# Fonte.net
KiCad netlist of a schematic drawn in Altium Designer
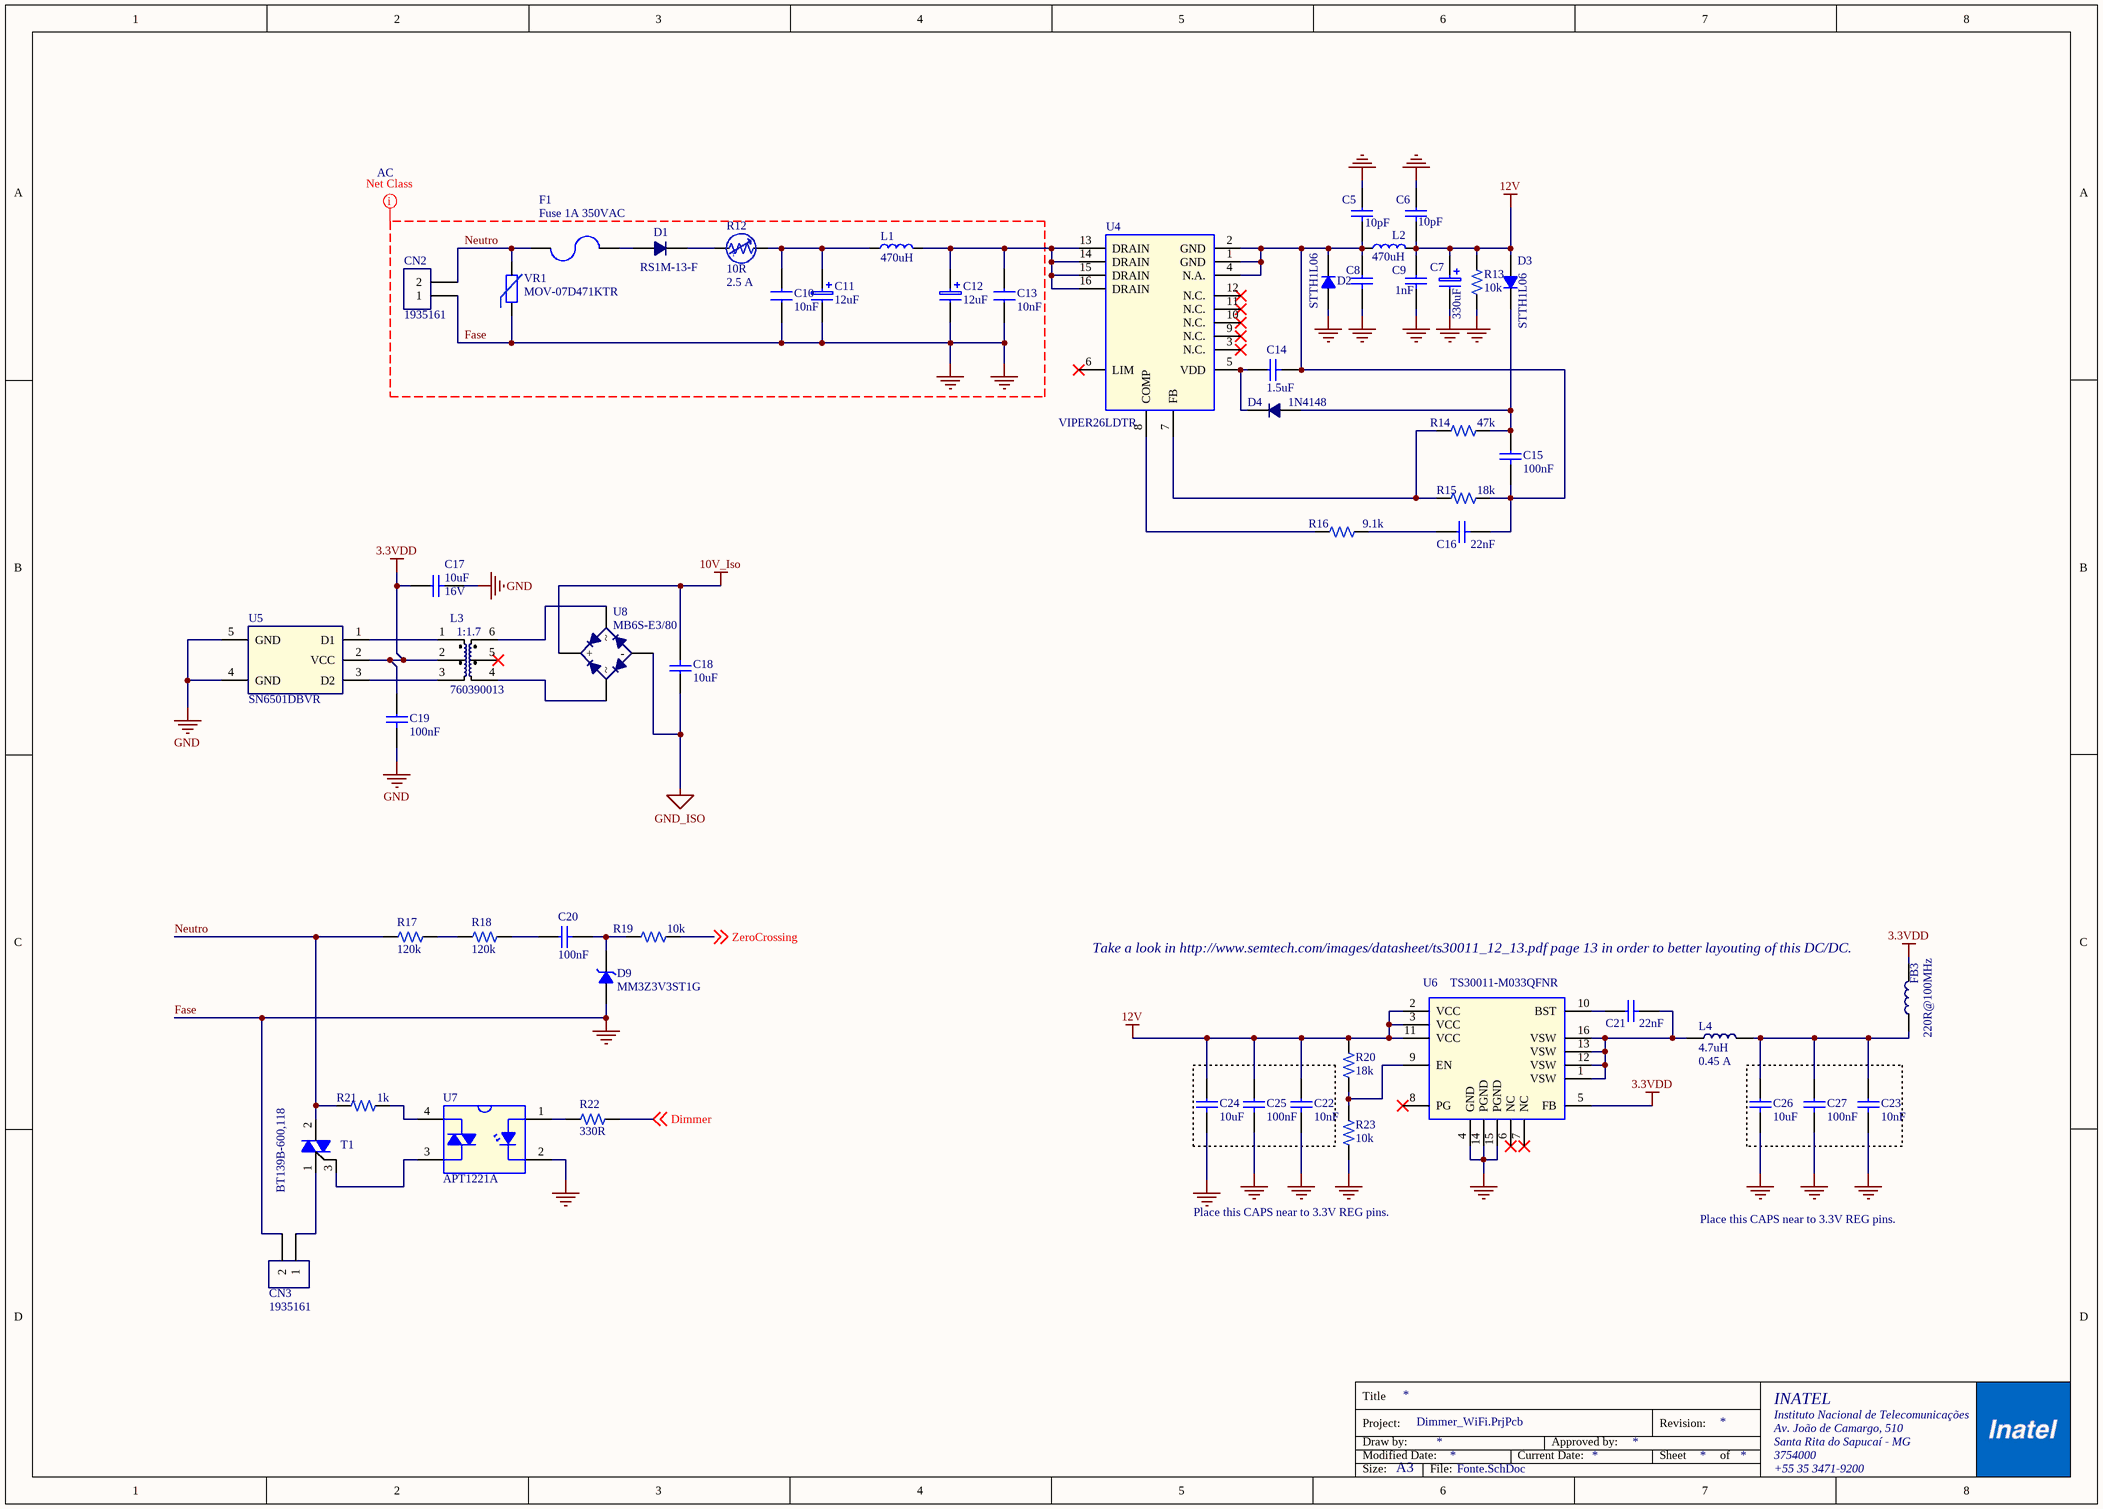
[diagram p0: Fonte.SchDoc]

(export (version "E")
  (design (tool "Eeschema 10.0.6"))
  (components
    (comp (ref "C5")
      (value "10pF")
      (footprint "0603-3D")
      (description "CAP CER 10PF 50V NP0 0603")
      (fields (field (name "VOLTAGE") "50V") (field (name "USER") "Rodrigo Villela"))
      (libsource (lib "CapacitoresPrjLib") (part "10pF 1% 0603 MLCC NPO 50V"))
    )
    (comp (ref "C6")
      (value "10pF")
      (footprint "0603-3D")
      (description "CAP CER 10PF 50V NP0 0603")
      (fields (field (name "VOLTAGE") "50V") (field (name "USER") "Rodrigo Villela"))
      (libsource (lib "CapacitoresPrjLib") (part "10pF 1% 0603 MLCC NPO 50V"))
    )
    (comp (ref "C7")
      (value "330uF")
      (footprint "CAP-RADIAL-630Dx1500Hx250P-3D")
      (description "CAP 330 UF 20% 16 V")
      (fields (field (name "VOLTAGE") "16V") (field (name "USER") "Jean Pierre"))
      (libsource (lib "LES") (part "330uF 20% RADIAL PTH 16V"))
    )
    (comp (ref "C8")
      (value "1nF")
      (footprint "0603-3D")
      (description "CAP CER 1000PF 50V 5% NP0 0603")
      (fields (field (name "VOLTAGE") "50V") (field (name "USER") "Anderson Daniel Soares"))
      (libsource (lib "CapacitoresPrjLib") (part "1000pF 5% 0603 MLCC NP0 50V"))
    )
    (comp (ref "C9")
      (value "1nF")
      (footprint "0603-3D")
      (description "CAP CER 1000PF 50V 5% NP0 0603")
      (fields (field (name "VOLTAGE") "50V") (field (name "USER") "Anderson Daniel Soares"))
      (libsource (lib "CapacitoresPrjLib") (part "1000pF 5% 0603 MLCC NP0 50V"))
    )
    (comp (ref "C10")
      (value "10nF")
      (footprint "CAP-RADIAL-5mm")
      (description "CAP FILM 10000PF 5% 630VDC RAD")
      (fields (field (name "VOLTAGE") "400VAC") (field (name "USER") "Ricardo Dias"))
      (libsource (lib "CapacitoresPrjLib") (part "10nF 5% RADIAL FILM 400VAC"))
    )
    (comp (ref "C11")
      (value "12uF")
      (footprint "CAP-RADIAL-1000Dx1750Hx500P-3D")
      (description "CAP ALUM 12UF 20% 350V RADIAL")
      (fields (field (name "VOLTAGE") "350V") (field (name "USER") "Ricardo Dias"))
      (libsource (lib "LES") (part "12uF 20% RADIAL PTH 350V"))
    )
    (comp (ref "C12")
      (value "12uF")
      (footprint "CAP-RADIAL-1000Dx1750Hx500P-3D")
      (description "CAP ALUM 12UF 20% 350V RADIAL")
      (fields (field (name "VOLTAGE") "350V") (field (name "USER") "Ricardo Dias"))
      (libsource (lib "LES") (part "12uF 20% RADIAL PTH 350V"))
    )
    (comp (ref "C13")
      (value "10nF")
      (footprint "CAP-RADIAL-5mm")
      (description "CAP FILM 10000PF 5% 630VDC RAD")
      (fields (field (name "VOLTAGE") "400VAC") (field (name "USER") "Ricardo Dias"))
      (libsource (lib "CapacitoresPrjLib") (part "10nF 5% RADIAL FILM 400VAC"))
    )
    (comp (ref "C14")
      (value "1.5uF")
      (footprint "1206-Ceramic-3D")
      (description "CAP CER 1.5UF 50V X7R 1206")
      (fields (field (name "VOLTAGE") "50V") (field (name "USER") "Ricardo Dias"))
      (libsource (lib "LES") (part "1.5uF 10% 1206 MLCC X7R 50V"))
    )
    (comp (ref "C15")
      (value "100nF")
      (footprint "0603-3D")
      (description "0.1µF ±10% 50V Ceramic Capacitor X7R 0603 (1608 Metric)")
      (fields (field (name "VOLTAGE") "50V") (field (name "USER") "Ricardo Dias"))
      (libsource (lib "CapacitoresPrjLib") (part "0.1uF 10% 0603 MLCC X7R 50V KEMET"))
    )
    (comp (ref "C16")
      (value "22nF")
      (footprint "0603-3D")
      (description "0.022µF 16V Ceramic Capacitor X7R 0603")
      (fields (field (name "VOLTAGE") "16V") (field (name "USER") "Jean Pierre"))
      (libsource (lib "CapacitoresPrjLib") (part "0.022uF 20% 0603 MLCC X7R 16V"))
    )
    (comp (ref "C17")
      (value "10uF")
      (footprint "CAP-0603-3D")
      (description "CAP CER 10UF 16V 20% X5R 0603")
      (fields (field (name "VOLTAGE") "16V") (field (name "USER") "Mateus Elias"))
      (libsource (lib "CapacitoresPrjLib") (part "10uF 20% 0603 MLCC X5R 16V"))
    )
    (comp (ref "C18")
      (value "10uF")
      (footprint "CAP-0603-3D")
      (description "CAP CER 10UF 16V 20% X5R 0603")
      (fields (field (name "VOLTAGE") "16V") (field (name "USER") "Mateus Elias"))
      (libsource (lib "CapacitoresPrjLib") (part "10uF 20% 0603 MLCC X5R 16V"))
    )
    (comp (ref "C19")
      (value "100nF")
      (footprint "0603-3D")
      (description "CAP CER 0.1UF 50V 10% X7R 0603")
      (fields (field (name "VOLTAGE") "50V") (field (name "USER") "Anderson Daniel Soares"))
      (libsource (lib "CapacitoresPrjLib") (part "0.1uF 10% 0603 MLCC X7R 50V"))
    )
    (comp (ref "C20")
      (value "100nF")
      (footprint "0603-3D")
      (description "CAP CER 0.1UF 50V 10% X7R 0603")
      (fields (field (name "VOLTAGE") "50V") (field (name "USER") "Anderson Daniel Soares"))
      (libsource (lib "CapacitoresPrjLib") (part "0.1uF 10% 0603 MLCC X7R 50V"))
    )
    (comp (ref "C21")
      (value "22nF")
      (footprint "0603-3D")
      (description "0.022µF 16V Ceramic Capacitor X7R 0603")
      (fields (field (name "VOLTAGE") "16V") (field (name "USER") "Jean Pierre"))
      (libsource (lib "CapacitoresPrjLib") (part "0.022uF 20% 0603 MLCC X7R 16V"))
    )
    (comp (ref "C22")
      (value "10nF")
      (footprint "0603-3D")
      (description "10000pF ±10% 16V Ceramic Capacitor X7R 0603 (1608 Metric)")
      (fields (field (name "VOLTAGE") "50V") (field (name "USER") "Ricardo Dias"))
      (libsource (lib "CapacitoresPrjLib") (part "10000pF 10% 0603 MLCC X7R 50V KEMET"))
    )
    (comp (ref "C23")
      (value "10nF")
      (footprint "0603-3D")
      (description "10000pF ±10% 16V Ceramic Capacitor X7R 0603 (1608 Metric)")
      (fields (field (name "VOLTAGE") "50V") (field (name "USER") "Ricardo Dias"))
      (libsource (lib "CapacitoresPrjLib") (part "10000pF 10% 0603 MLCC X7R 50V KEMET"))
    )
    (comp (ref "C24")
      (value "10uF")
      (footprint "CAP-0603-3D")
      (description "CAP CER 10UF 16V 20% X5R 0603")
      (fields (field (name "VOLTAGE") "16V") (field (name "USER") "Mateus Elias"))
      (libsource (lib "CapacitoresPrjLib") (part "10uF 20% 0603 MLCC X5R 16V"))
    )
    (comp (ref "C25")
      (value "100nF")
      (footprint "0603-3D")
      (description "CAP CER 0.1UF 50V 10% X7R 0603")
      (fields (field (name "VOLTAGE") "50V") (field (name "USER") "Anderson Daniel Soares"))
      (libsource (lib "CapacitoresPrjLib") (part "0.1uF 10% 0603 MLCC X7R 50V"))
    )
    (comp (ref "C26")
      (value "10uF")
      (footprint "CAP-0603-3D")
      (description "CAP CER 10UF 16V 20% X5R 0603")
      (fields (field (name "VOLTAGE") "16V") (field (name "USER") "Mateus Elias"))
      (libsource (lib "CapacitoresPrjLib") (part "10uF 20% 0603 MLCC X5R 16V"))
    )
    (comp (ref "C27")
      (value "100nF")
      (footprint "0603-3D")
      (description "CAP CER 0.1UF 50V 10% X7R 0603")
      (fields (field (name "VOLTAGE") "50V") (field (name "USER") "Anderson Daniel Soares"))
      (libsource (lib "CapacitoresPrjLib") (part "0.1uF 10% 0603 MLCC X7R 50V"))
    )
    (comp (ref "CN2")
      (value "1935161")
      (footprint "TERM BLOCK PCB 2POS 5.0MM")
      (description "TERM BLOCK PCB 2POS 5.0MM")
      (fields (field (name "USER") "Rodrigo Balbi"))
      (libsource (lib "") (part "1935161  TERM BLOCK PCB 2X1_1"))
    )
    (comp (ref "CN3")
      (value "1935161")
      (footprint "TERM BLOCK PCB 2POS 5.0MM")
      (description "TERM BLOCK PCB 2POS 5.0MM")
      (fields (field (name "USER") "Rodrigo Balbi"))
      (libsource (lib "Conectores") (part "1935161  TERM BLOCK PCB 2X1"))
    )
    (comp (ref "D1")
      (value "RS1M-13-F")
      (footprint "DO-214AC_SMA-3D")
      (description "DIODE GEN PURP 1KV 1A SMA")
      (fields (field (name "MANUFACTURER") "Diodes Incorporated") (field (name "USER") "Pedro Vilela"))
      (libsource (lib "Diodos") (part "RS1M-13-F DIODE GEN PURP 1KV 1A SMA"))
    )
    (comp (ref "D2")
      (value "STTH1L06")
      (footprint "DO-214AC_SMA-3D")
      (description "DIODE GEN PURP 600V 1A SMA")
      (fields (field (name "USER") "Rafael Magalhães de Barros"))
      (libsource (lib "Diodos") (part "STTH1L06 TURBO 2 ULTRAFAST HIGH VOLTAGE RECTIFIER"))
    )
    (comp (ref "D3")
      (value "STTH1L06")
      (footprint "DO-214AC_SMA-3D")
      (description "DIODE GEN PURP 600V 1A SMA")
      (fields (field (name "USER") "Rafael Magalhães de Barros"))
      (libsource (lib "Diodos") (part "STTH1L06 TURBO 2 ULTRAFAST HIGH VOLTAGE RECTIFIER"))
    )
    (comp (ref "D4")
      (value "1N4148")
      (footprint "SOD323-3D")
      (description "DIODE SWITCHING 75V 0.15A SOD323")
      (fields (field (name "USER") "Mateus Elias"))
      (libsource (lib "Diodos") (part "1N4148 FAST SWITCHING DIODE"))
    )
    (comp (ref "D9")
      (value "MM3Z3V3ST1G")
      (footprint "SOD323-3D")
      (description "DIODE ZENER 3.3V 200MW SOD323")
      (fields (field (name "USER") "Ricardo Dias"))
      (libsource (lib "LES") (part "MM3Z3V3ST1G 3.3V DIODE ZENER"))
    )
    (comp (ref "F1")
      (value "Fuse 1A 350VAC")
      (footprint "Fuse-SMD-610L254W279H-3D")
      (description "FUSE BOARD MNT 1A 350VAC 72VDC")
      (fields (field (name "USER") "Mateus Elias"))
      (libsource (lib "DiversosPrjLib") (part "Fuse Board SMD2410 350VAC 72VDC"))
    )
    (comp (ref "FB3")
      (value "220R@100MHz")
      (footprint "IND-0603-3D")
      (description "FERRITE CHIP 0603 220 OHM")
      (fields (field (name "USER") "Jean Pierre"))
      (libsource (lib "IndutoresPrjLib") (part "220R@100MHz 0603 FB 0.05R 2A"))
    )
    (comp (ref "L1")
      (value "470uH")
      (footprint "IND_620W590L450H_CLF6045")
      (description "FIXED IND 470UH 370MA 1.42 OHM")
      (fields (field (name "USER") "Jean Pierre"))
      (libsource (lib "LES") (part "470uH 20% SMDPWR WW 0.37A"))
    )
    (comp (ref "L2")
      (value "470uH")
      (footprint "IND_620W590L450H_CLF6045")
      (description "FIXED IND 470UH 370MA 1.42 OHM")
      (fields (field (name "USER") "Jean Pierre"))
      (libsource (lib "LES") (part "470uH 20% SMDPWR WW 0.37A"))
    )
    (comp (ref "L3")
      (value "760390013")
      (footprint "TRAFO-DC/DC-CONVERTERS-3D")
      (description "TRANSFORMER 475UH SMD")
      (fields (field (name "USER") "Ricardo Dias"))
      (libsource (lib "IndutoresPrjLib") (part "760390013 TRANSFORMER 475UH SMD"))
    )
    (comp (ref "L4")
      (value "4.7uH")
      (footprint "IND-1210-PWR-3D")
      (description "FIXED IND 4.7UH 450MA 200 MOHM")
      (fields (field (name "CURRENT RATING") "0.45 A") (field (name "USER") "Jean Pierre"))
      (libsource (lib "IndutoresPrjLib") (part "4.7uH SMD WW 0.2R 0.45A"))
    )
    (comp (ref "R12")
      (value "10R")
      (footprint "NTC-800D500W-500P-3D")
      (description "ICL 10 OHM 20% 2.5A 8MM")
      (fields
        (field (name "TOLERANCE") "20%")
        (field (name "CURRENT") "2.5 A")
        (field (name "USER") "Jean Pierre")
      )
      (libsource (lib "DiversosPrjLib") (part "SL08 10002 NTC 10R 20% 2.5A 8MM"))
    )
    (comp (ref "R13")
      (value "10k")
      (footprint "0603-3D")
      (description "RES SMD 10K OHM 1% 1/10W 0603")
      (fields
        (field (name "MANUFACTURER") "Yageo")
        (field (name "MANUFACTURER PART NUMBER") "RC0603FR-0710KL")
        (field (name "USER") "Pedro Vilela")
      )
      (libsource (lib "ResitoresPrjLib") (part "10k 1% 0603 TNF 1/10W"))
    )
    (comp (ref "R14")
      (value "47k")
      (footprint "0603-3D")
      (description "RES SMD 47K OHM 1% 1/10W 0603")
      (fields (field (name "USER") "Anderson Daniel Soares"))
      (libsource (lib "ResitoresPrjLib") (part "47k 1% 0603 TKF 1/16W"))
    )
    (comp (ref "R15")
      (value "18k")
      (footprint "0603-3D")
      (description "RES SMD 18K OHM 1% 1/10W 0603")
      (fields (field (name "TOLERANCE") "1%") (field (name "USER") "Ricardo Dias"))
      (libsource (lib "ResitoresPrjLib") (part "18k 1% 0603 TKF 1/10W"))
    )
    (comp (ref "R16")
      (value "9.1k")
      (footprint "0603-3D")
      (description "RES SMD 9.1K OHM 1% 1/10W 0603")
      (fields (field (name "USER") "Ricardo Dias"))
      (libsource (lib "ResitoresPrjLib") (part "9.1k 1% 0603 TKF 1/10W"))
    )
    (comp (ref "R17")
      (value "120k")
      (footprint "RES-1206-3D")
      (description "RES SMD 120K OHM 5% 1/4W 1206")
      (fields (field (name "TOLERANCE") "5%") (field (name "USER") "Rodrigo Villela"))
      (libsource (lib "ResitoresPrjLib") (part "120k 5% 1206 TKF 1/4W"))
    )
    (comp (ref "R18")
      (value "120k")
      (footprint "RES-1206-3D")
      (description "RES SMD 120K OHM 5% 1/4W 1206")
      (fields (field (name "TOLERANCE") "5%") (field (name "USER") "Rodrigo Villela"))
      (libsource (lib "ResitoresPrjLib") (part "120k 5% 1206 TKF 1/4W"))
    )
    (comp (ref "R19")
      (value "10k")
      (footprint "0603-3D")
      (description "RES SMD 10K OHM 1% 1/10W 0603")
      (fields
        (field (name "MANUFACTURER") "Yageo")
        (field (name "MANUFACTURER PART NUMBER") "RC0603FR-0710KL")
        (field (name "USER") "Pedro Vilela")
      )
      (libsource (lib "ResitoresPrjLib") (part "10k 1% 0603 TNF 1/10W"))
    )
    (comp (ref "R20")
      (value "18k")
      (footprint "0603-3D")
      (description "RES SMD 18K OHM 1% 1/10W 0603")
      (fields (field (name "TOLERANCE") "1%") (field (name "USER") "Ricardo Dias"))
      (libsource (lib "ResitoresPrjLib") (part "18k 1% 0603 TKF 1/10W"))
    )
    (comp (ref "R21")
      (value "1k")
      (footprint "0805-3D")
      (description "RES SMD 1K OHM 1% 1/8W 0805")
      (fields (field (name "USER") "Mateus Elias"))
      (libsource (lib "ResitoresPrjLib") (part "1k 1% 0805 TKF 1/8W"))
    )
    (comp (ref "R22")
      (value "330R")
      (footprint "0603-3D")
      (description "RES SMD 330 OHM 5% 1/10W 0603")
      (fields (field (name "TOLERANCE") "5%") (field (name "USER") "Luiz F Siecola"))
      (libsource (lib "ResitoresPrjLib") (part "330R 5% 0603 TKF 1/10W"))
    )
    (comp (ref "R23")
      (value "10k")
      (footprint "0603-3D")
      (description "RES SMD 10K OHM 1% 1/10W 0603")
      (fields
        (field (name "MANUFACTURER") "Yageo")
        (field (name "MANUFACTURER PART NUMBER") "RC0603FR-0710KL")
        (field (name "USER") "Pedro Vilela")
      )
      (libsource (lib "ResitoresPrjLib") (part "10k 1% 0603 TNF 1/10W"))
    )
    (comp (ref "T1")
      (value "BT139B-600,118")
      (footprint "D2PAC-3D")
      (description "TRIAC 600V 16A D2PAK")
      (fields (field (name "USER") "Jean Pierre"))
      (libsource (lib "Transistores") (part "BT139B-600,118 TRIAC GEN PURPOSE"))
    )
    (comp (ref "U4")
      (value "VIPER26LDTR")
      (footprint "SO16N-3D")
      (description "IC OFFLINE CONV PWM 800V 16-SOIC")
      (fields (field (name "USER") "Ricardo Dias"))
      (libsource (lib "LES") (part "VIPER26LDTR CONVERTER CA/CC FIXED FREQ"))
    )
    (comp (ref "U5")
      (value "SN6501DBVR")
      (footprint "SOT23-5")
      (description "IC REG CONV PWR SUPPLIES SOT23-5")
      (fields (field (name "USER") "Ricardo Dias"))
      (libsource (lib "Circuito Integrado") (part "SN6501DBVR REG CONV ISO PWR SUPPLIES SOT23-5"))
    )
    (comp (ref "U6")
      (value "TS30011-M033QFNR")
      (footprint "16VQFN-3D")
      (description "IC REG BUCK 3.3V 1A SYNC 16-VQFN")
      (fields (field (name "USER") "Ricardo Dias"))
      (libsource (lib "LES") (part "TS30011-M033QFNR DC/DC 3.3V FIX 1A 1.5MHz"))
    )
    (comp (ref "U7")
      (value "APT1221A")
      (footprint "DIP4-SMD")
      (description "Optoisolator Triac Output 5000Vrms 1 Channel 4-SMD")
      (fields (field (name "USER") "Luiz Fernando"))
      (libsource (lib "Circuito Integrado") (part "APT1221A"))
    )
    (comp (ref "U8")
      (value "MB6S-E3/80")
      (footprint "TO-269AA-3D")
      (description "Bridge Rectifier Single Phase 600V 500mA Surface Mount TO-269AA (MBS)")
      (fields (field (name "USER") "Reis"))
      (libsource (lib "Diodos") (part "MB6S-E3/80 BRIDGE RECTIFIER SINGLE"))
    )
    (comp (ref "VR1")
      (value "MOV-07D471KTR")
      (footprint "VAR-05D-SERIES-PTH-3D")
      (description "MOV-07D471KTR - VARISTOR 470V 1.2KA DISC 7MM")
      (fields (field (name "USER") "Luiz F Siecola"))
      (libsource (lib "DiversosPrjLib") (part "MOV-07D471KTR VAR 470V 1.2KA DISC 7MM"))
    )
  )
  (nets
    (net (code "1") (name "/Neutro") (class "Default")
      (node (ref "CN2") (pin "2") (pinfunction "2_2") (pintype "passive"))
      (node (ref "F1") (pin "2") (pinfunction "2_2") (pintype "passive"))
      (node (ref "R17") (pin "1") (pinfunction "1_1") (pintype "passive"))
      (node (ref "R21") (pin "2") (pinfunction "2_2") (pintype "passive"))
      (node (ref "T1") (pin "2") (pinfunction "T2_2") (pintype "passive"))
      (node (ref "VR1") (pin "2") (pinfunction "2_2") (pintype "passive"))
    )
    (net (code "2") (name "3.3VDD") (class "Default")
      (node (ref "C17") (pin "1") (pinfunction "1_1") (pintype "passive"))
      (node (ref "C19") (pin "1") (pinfunction "1_1") (pintype "passive"))
      (node (ref "FB3") (pin "2") (pinfunction "2_2") (pintype "passive"))
      (node (ref "L3") (pin "2") (pinfunction "2_2") (pintype "passive"))
      (node (ref "U5") (pin "2") (pinfunction "VCC_2") (pintype "passive"))
      (node (ref "U6") (pin "5") (pinfunction "FB_5") (pintype "passive"))
    )
    (net (code "3") (name "10V_Iso") (class "Default")
      (node (ref "C18") (pin "2") (pinfunction "2_2") (pintype "passive"))
      (node (ref "U8") (pin "3") (pinfunction "+_3") (pintype "passive"))
    )
    (net (code "4") (name "12V") (class "Default")
      (node (ref "C22") (pin "1") (pinfunction "1_1") (pintype "passive"))
      (node (ref "C24") (pin "1") (pinfunction "1_1") (pintype "passive"))
      (node (ref "C25") (pin "1") (pinfunction "1_1") (pintype "passive"))
      (node (ref "C6") (pin "2") (pinfunction "2_2") (pintype "passive"))
      (node (ref "C7") (pin "1") (pinfunction "1_1") (pintype "passive"))
      (node (ref "C9") (pin "1") (pinfunction "1_1") (pintype "passive"))
      (node (ref "D3") (pin "1") (pinfunction "1_1") (pintype "passive"))
      (node (ref "L2") (pin "2") (pinfunction "2_2") (pintype "passive"))
      (node (ref "R13") (pin "2") (pinfunction "2_2") (pintype "passive"))
      (node (ref "R20") (pin "2") (pinfunction "2_2") (pintype "passive"))
      (node (ref "U6") (pin "11") (pinfunction "VCC_11") (pintype "passive"))
      (node (ref "U6") (pin "2") (pinfunction "VCC_2") (pintype "passive"))
      (node (ref "U6") (pin "3") (pinfunction "VCC_3") (pintype "passive"))
    )
    (net (code "5") (name "Dimmer") (class "Default")
      (node (ref "R22") (pin "2") (pinfunction "2_2") (pintype "passive"))
    )
    (net (code "6") (name "GND") (class "Default")
      (node (ref "C10") (pin "2") (pinfunction "2_2") (pintype "passive"))
      (node (ref "C11") (pin "2") (pinfunction "2_2") (pintype "passive"))
      (node (ref "C12") (pin "2") (pinfunction "2_2") (pintype "passive"))
      (node (ref "C13") (pin "2") (pinfunction "2_2") (pintype "passive"))
      (node (ref "C17") (pin "2") (pinfunction "2_2") (pintype "passive"))
      (node (ref "C19") (pin "2") (pinfunction "2_2") (pintype "passive"))
      (node (ref "C22") (pin "2") (pinfunction "2_2") (pintype "passive"))
      (node (ref "C23") (pin "2") (pinfunction "2_2") (pintype "passive"))
      (node (ref "C24") (pin "2") (pinfunction "2_2") (pintype "passive"))
      (node (ref "C25") (pin "2") (pinfunction "2_2") (pintype "passive"))
      (node (ref "C26") (pin "2") (pinfunction "2_2") (pintype "passive"))
      (node (ref "C27") (pin "2") (pinfunction "2_2") (pintype "passive"))
      (node (ref "C5") (pin "1") (pinfunction "1_1") (pintype "passive"))
      (node (ref "C6") (pin "1") (pinfunction "1_1") (pintype "passive"))
      (node (ref "C7") (pin "2") (pinfunction "2_2") (pintype "passive"))
      (node (ref "C8") (pin "2") (pinfunction "2_2") (pintype "passive"))
      (node (ref "C9") (pin "2") (pinfunction "2_2") (pintype "passive"))
      (node (ref "CN2") (pin "1") (pinfunction "1_1") (pintype "passive"))
      (node (ref "CN3") (pin "2") (pinfunction "2_2") (pintype "passive"))
      (node (ref "D2") (pin "1") (pinfunction "1_1") (pintype "passive"))
      (node (ref "D9") (pin "1") (pinfunction "1_1") (pintype "passive"))
      (node (ref "R13") (pin "1") (pinfunction "1_1") (pintype "passive"))
      (node (ref "R23") (pin "1") (pinfunction "1_1") (pintype "passive"))
      (node (ref "U5") (pin "4") (pinfunction "GND_4") (pintype "passive"))
      (node (ref "U5") (pin "5") (pinfunction "GND_5") (pintype "passive"))
      (node (ref "U6") (pin "14") (pinfunction "PGND_14") (pintype "passive"))
      (node (ref "U6") (pin "15") (pinfunction "PGND_15") (pintype "passive"))
      (node (ref "U6") (pin "4") (pinfunction "GND_4") (pintype "passive"))
      (node (ref "U7") (pin "2") (pinfunction "K_2") (pintype "passive"))
      (node (ref "VR1") (pin "1") (pinfunction "1_1") (pintype "passive"))
    )
    (net (code "7") (name "GND_ISO") (class "Default")
      (node (ref "C18") (pin "1") (pinfunction "1_1") (pintype "passive"))
      (node (ref "U8") (pin "4") (pinfunction "-_4") (pintype "passive"))
    )
    (net (code "8") (name "Net-(C10-Pad1)") (class "Default")
      (node (ref "C10") (pin "1") (pinfunction "1_1") (pintype "passive"))
      (node (ref "C11") (pin "1") (pinfunction "1_1") (pintype "passive"))
      (node (ref "L1") (pin "1") (pinfunction "1_1") (pintype "passive"))
      (node (ref "R12") (pin "2") (pinfunction "2_2") (pintype "passive"))
    )
    (net (code "9") (name "Net-(C12-Pad1)") (class "Default")
      (node (ref "C12") (pin "1") (pinfunction "1_1") (pintype "passive"))
      (node (ref "C13") (pin "1") (pinfunction "1_1") (pintype "passive"))
      (node (ref "L1") (pin "2") (pinfunction "2_2") (pintype "passive"))
      (node (ref "U4") (pin "13") (pinfunction "DRAIN_13") (pintype "passive"))
      (node (ref "U4") (pin "14") (pinfunction "DRAIN_14") (pintype "passive"))
      (node (ref "U4") (pin "15") (pinfunction "DRAIN_15") (pintype "passive"))
      (node (ref "U4") (pin "16") (pinfunction "DRAIN_16") (pintype "passive"))
    )
    (net (code "10") (name "Net-(C15-Pad1)") (class "Default")
      (node (ref "C15") (pin "1") (pinfunction "1_1") (pintype "passive"))
      (node (ref "D3") (pin "2") (pinfunction "2_2") (pintype "passive"))
      (node (ref "D4") (pin "1") (pinfunction "1_1") (pintype "passive"))
      (node (ref "R14") (pin "2") (pinfunction "2_2") (pintype "passive"))
    )
    (net (code "11") (name "Net-(C16-Pad1)") (class "Default")
      (node (ref "C16") (pin "1") (pinfunction "1_1") (pintype "passive"))
      (node (ref "R16") (pin "2") (pinfunction "2_2") (pintype "passive"))
    )
    (net (code "12") (name "Net-(C20-Pad1)") (class "Default")
      (node (ref "C20") (pin "1") (pinfunction "1_1") (pintype "passive"))
      (node (ref "R18") (pin "2") (pinfunction "2_2") (pintype "passive"))
    )
    (net (code "13") (name "Net-(C20-Pad2)") (class "Default")
      (node (ref "C20") (pin "2") (pinfunction "2_2") (pintype "passive"))
      (node (ref "D9") (pin "2") (pinfunction "2_2") (pintype "passive"))
      (node (ref "R19") (pin "1") (pinfunction "1_1") (pintype "passive"))
    )
    (net (code "14") (name "Net-(C21-Pad2)") (class "Default")
      (node (ref "C21") (pin "2") (pinfunction "2_2") (pintype "passive"))
      (node (ref "L4") (pin "1") (pinfunction "1_1") (pintype "passive"))
      (node (ref "U6") (pin "1") (pinfunction "VSW_1") (pintype "passive"))
      (node (ref "U6") (pin "12") (pinfunction "VSW_12") (pintype "passive"))
      (node (ref "U6") (pin "13") (pinfunction "VSW_13") (pintype "passive"))
      (node (ref "U6") (pin "16") (pinfunction "VSW_16") (pintype "passive"))
    )
    (net (code "15") (name "Net-(C23-Pad1)") (class "Default")
      (node (ref "C23") (pin "1") (pinfunction "1_1") (pintype "passive"))
      (node (ref "C26") (pin "1") (pinfunction "1_1") (pintype "passive"))
      (node (ref "C27") (pin "1") (pinfunction "1_1") (pintype "passive"))
      (node (ref "FB3") (pin "1") (pinfunction "1_1") (pintype "passive"))
      (node (ref "L4") (pin "2") (pinfunction "2_2") (pintype "passive"))
    )
    (net (code "16") (name "Net-(D1-Pad1)") (class "Default")
      (node (ref "D1") (pin "1") (pinfunction "1_1") (pintype "passive"))
      (node (ref "F1") (pin "1") (pinfunction "1_1") (pintype "passive"))
    )
    (net (code "17") (name "Net-(D1-Pad2)") (class "Default")
      (node (ref "D1") (pin "2") (pinfunction "2_2") (pintype "passive"))
      (node (ref "R12") (pin "1") (pinfunction "1_1") (pintype "passive"))
    )
    (net (code "18") (name "Net-(L3-Pad4)") (class "Default")
      (node (ref "L3") (pin "4") (pinfunction "4_4") (pintype "passive"))
      (node (ref "U8") (pin "1") (pinfunction "~_1") (pintype "passive"))
    )
    (net (code "19") (name "Net-(L3-Pad6)") (class "Default")
      (node (ref "L3") (pin "6") (pinfunction "6_6") (pintype "passive"))
      (node (ref "U8") (pin "2") (pinfunction "~_2") (pintype "passive"))
    )
    (net (code "20") (name "Net-(R17-Pad2)") (class "Default")
      (node (ref "R17") (pin "2") (pinfunction "2_2") (pintype "passive"))
      (node (ref "R18") (pin "1") (pinfunction "1_1") (pintype "passive"))
    )
    (net (code "21") (name "Net-(T1-G)") (class "Default")
      (node (ref "T1") (pin "3") (pinfunction "G_3") (pintype "passive"))
      (node (ref "U7") (pin "3") (pinfunction "MT2_3") (pintype "passive"))
    )
    (net (code "22") (name "Net-(T1-T1)") (class "Default")
      (node (ref "CN3") (pin "1") (pinfunction "1_1") (pintype "passive"))
      (node (ref "T1") (pin "1") (pinfunction "T1_1") (pintype "passive"))
    )
    (net (code "23") (name "Net-(U4-COMP)") (class "Default")
      (node (ref "R16") (pin "1") (pinfunction "1_1") (pintype "passive"))
      (node (ref "U4") (pin "8") (pinfunction "COMP_8") (pintype "passive"))
    )
    (net (code "24") (name "Net-(U4-FB)") (class "Default")
      (node (ref "R14") (pin "1") (pinfunction "1_1") (pintype "passive"))
      (node (ref "R15") (pin "1") (pinfunction "1_1") (pintype "passive"))
      (node (ref "U4") (pin "7") (pinfunction "FB_7") (pintype "passive"))
    )
    (net (code "25") (name "Net-(U4-N.A.)") (class "Default")
      (node (ref "C14") (pin "2") (pinfunction "2_2") (pintype "passive"))
      (node (ref "C15") (pin "2") (pinfunction "2_2") (pintype "passive"))
      (node (ref "C16") (pin "2") (pinfunction "2_2") (pintype "passive"))
      (node (ref "C5") (pin "2") (pinfunction "2_2") (pintype "passive"))
      (node (ref "C8") (pin "1") (pinfunction "1_1") (pintype "passive"))
      (node (ref "D2") (pin "2") (pinfunction "2_2") (pintype "passive"))
      (node (ref "L2") (pin "1") (pinfunction "1_1") (pintype "passive"))
      (node (ref "R15") (pin "2") (pinfunction "2_2") (pintype "passive"))
      (node (ref "U4") (pin "1") (pinfunction "GND_1") (pintype "passive"))
      (node (ref "U4") (pin "2") (pinfunction "GND_2") (pintype "passive"))
      (node (ref "U4") (pin "4") (pinfunction "N.A._4") (pintype "passive"))
    )
    (net (code "26") (name "Net-(U4-VDD)") (class "Default")
      (node (ref "C14") (pin "1") (pinfunction "1_1") (pintype "passive"))
      (node (ref "D4") (pin "2") (pinfunction "2_2") (pintype "passive"))
      (node (ref "U4") (pin "5") (pinfunction "VDD_5") (pintype "passive"))
    )
    (net (code "27") (name "Net-(U5-D1)") (class "Default")
      (node (ref "L3") (pin "1") (pinfunction "1_1") (pintype "passive"))
      (node (ref "U5") (pin "1") (pinfunction "D1_1") (pintype "passive"))
    )
    (net (code "28") (name "Net-(U5-D2)") (class "Default")
      (node (ref "L3") (pin "3") (pinfunction "3_3") (pintype "passive"))
      (node (ref "U5") (pin "3") (pinfunction "D2_3") (pintype "passive"))
    )
    (net (code "29") (name "Net-(U6-BST)") (class "Default")
      (node (ref "C21") (pin "1") (pinfunction "1_1") (pintype "passive"))
      (node (ref "U6") (pin "10") (pinfunction "BST_10") (pintype "passive"))
    )
    (net (code "30") (name "Net-(U6-EN)") (class "Default")
      (node (ref "R20") (pin "1") (pinfunction "1_1") (pintype "passive"))
      (node (ref "R23") (pin "2") (pinfunction "2_2") (pintype "passive"))
      (node (ref "U6") (pin "9") (pinfunction "EN_9") (pintype "passive"))
    )
    (net (code "31") (name "Net-(U7-A)") (class "Default")
      (node (ref "R22") (pin "1") (pinfunction "1_1") (pintype "passive"))
      (node (ref "U7") (pin "1") (pinfunction "A_1") (pintype "passive"))
    )
    (net (code "32") (name "Net-(U7-T2)") (class "Default")
      (node (ref "R21") (pin "1") (pinfunction "1_1") (pintype "passive"))
      (node (ref "U7") (pin "4") (pinfunction "T2_4") (pintype "passive"))
    )
    (net (code "33") (name "ZeroCrossing") (class "Default")
      (node (ref "R19") (pin "2") (pinfunction "2_2") (pintype "passive"))
    )
    (net (code "34") (name "unconnected-(L3-Pad5)") (class "Default")
      (node (ref "L3") (pin "5") (pinfunction "5_5") (pintype "passive+no_connect"))
    )
    (net (code "35") (name "unconnected-(U4-LIM-Pad6)") (class "Default")
      (node (ref "U4") (pin "6") (pinfunction "LIM_6") (pintype "passive+no_connect"))
    )
    (net (code "36") (name "unconnected-(U4-N.C.-Pad3)") (class "Default")
      (node (ref "U4") (pin "3") (pinfunction "N.C._3") (pintype "passive+no_connect"))
    )
    (net (code "37") (name "unconnected-(U4-N.C.-Pad9)") (class "Default")
      (node (ref "U4") (pin "9") (pinfunction "N.C._9") (pintype "passive+no_connect"))
    )
    (net (code "38") (name "unconnected-(U4-N.C.-Pad10)") (class "Default")
      (node (ref "U4") (pin "10") (pinfunction "N.C._10") (pintype "passive+no_connect"))
    )
    (net (code "39") (name "unconnected-(U4-N.C.-Pad11)") (class "Default")
      (node (ref "U4") (pin "11") (pinfunction "N.C._11") (pintype "passive+no_connect"))
    )
    (net (code "40") (name "unconnected-(U4-N.C.-Pad12)") (class "Default")
      (node (ref "U4") (pin "12") (pinfunction "N.C._12") (pintype "passive+no_connect"))
    )
    (net (code "41") (name "unconnected-(U6-NC-Pad6)") (class "Default")
      (node (ref "U6") (pin "6") (pinfunction "NC_6") (pintype "passive+no_connect"))
    )
    (net (code "42") (name "unconnected-(U6-NC-Pad7)") (class "Default")
      (node (ref "U6") (pin "7") (pinfunction "NC_7") (pintype "passive+no_connect"))
    )
    (net (code "43") (name "unconnected-(U6-PG-Pad8)") (class "Default")
      (node (ref "U6") (pin "8") (pinfunction "PG_8") (pintype "passive+no_connect"))
    )
  )
)
